# Sheet2_1.net
KiCad netlist of a schematic drawn in Altium Designer
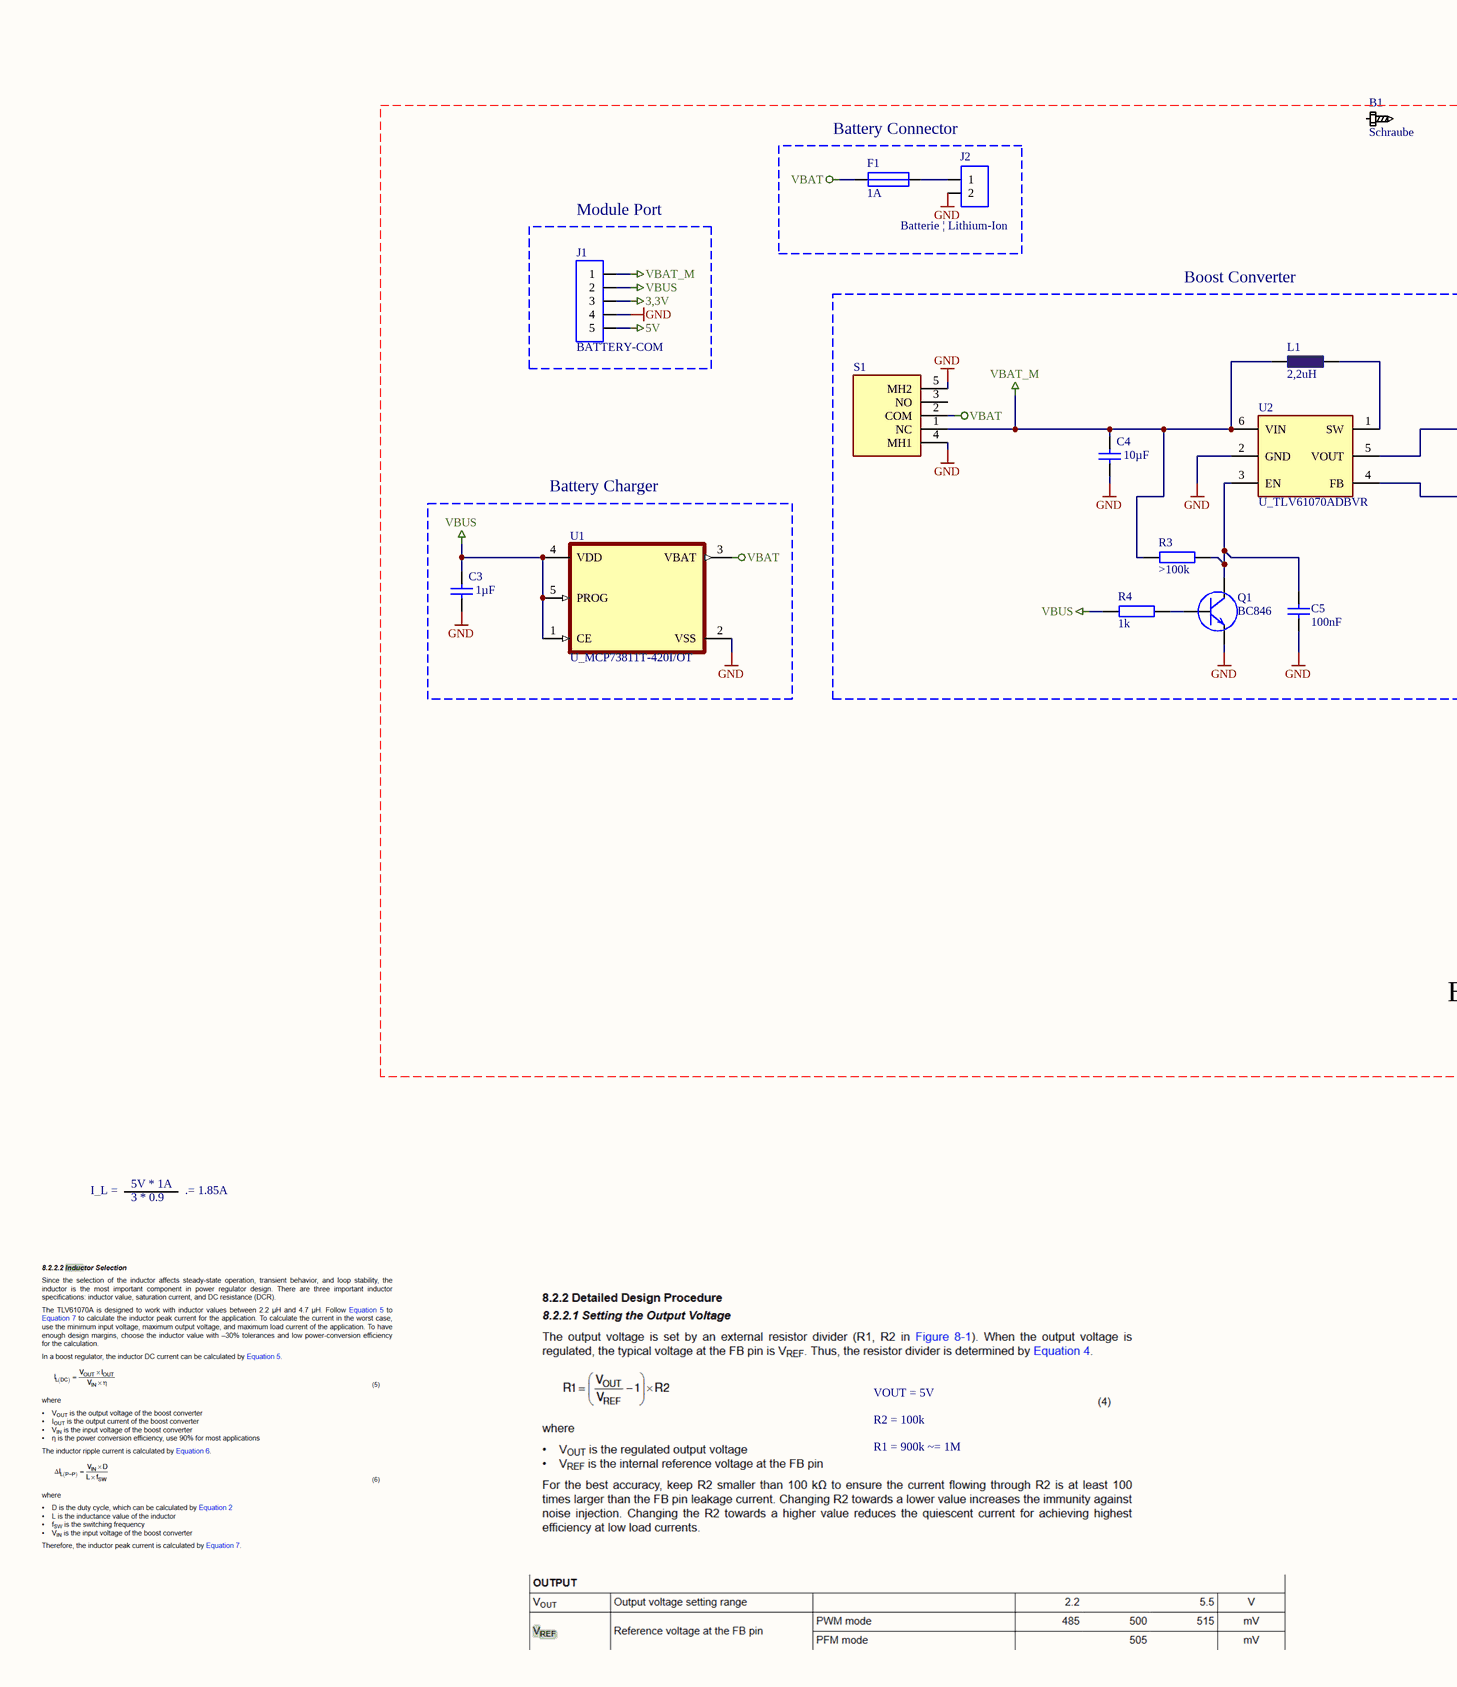
[diagram p0: Sheet2 (1).SchDoc, left]
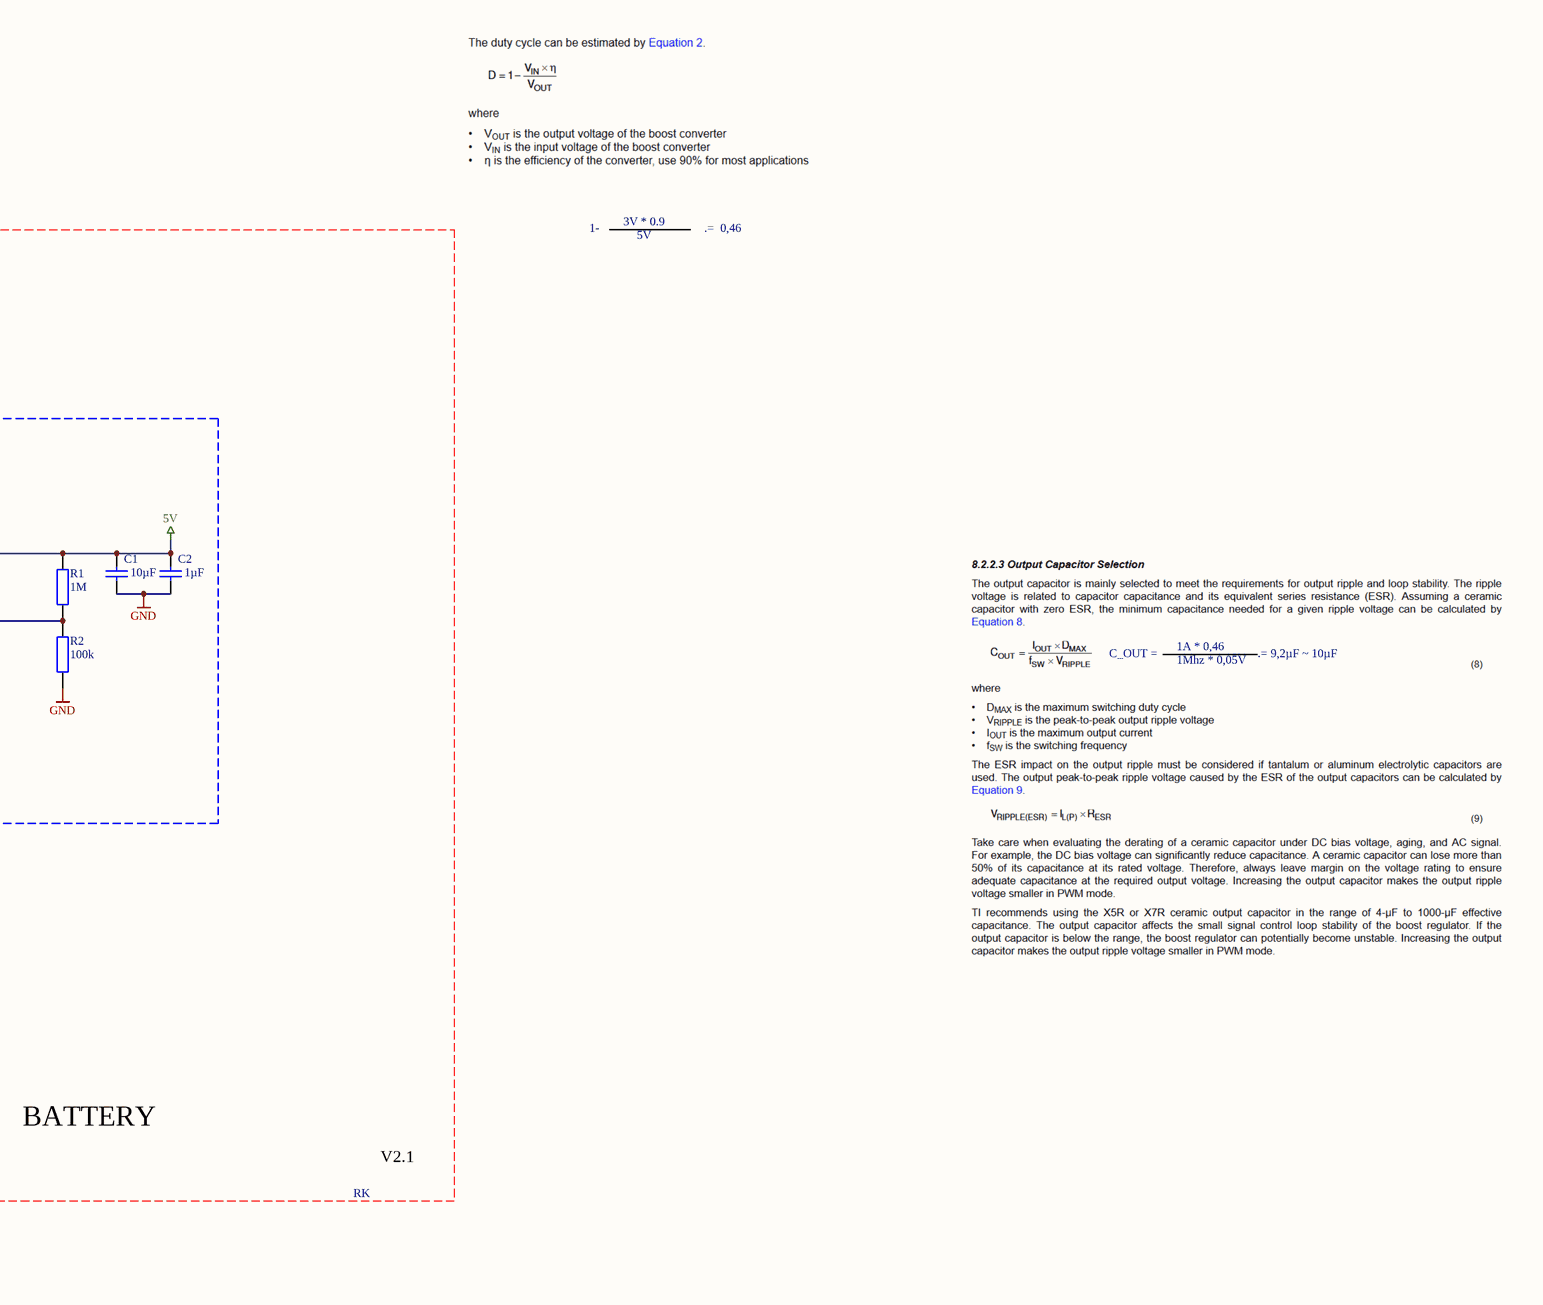
[diagram p1: Sheet2 (1).SchDoc, right]

(export (version "E")
  (design (tool "Eeschema 10.0.6"))
  (components
    (comp (ref "B1")
      (value "Schraube")
      (footprint "B_Schraube-M3 PAD")
      (description "Schraubenloch für M3 Schrauben")
      (libsource (lib "SCHLIB-PCSB_5.1.3") (part "B_Schraube"))
    )
    (comp (ref "C1")
      (value "10µF")
      (footprint "C_SMD_0805")
      (description "Kondensator SMD Universal, Keramik, Folie, usw.")
      (libsource (lib "SCHLIB-PCSB_5.1.3") (part "C_SMD_KO"))
    )
    (comp (ref "C2")
      (value "1µF")
      (footprint "C_SMD_0603")
      (description "Kondensator SMD Universal, Keramik, Folie, usw.")
      (libsource (lib "SCHLIB-PCSB_5.1.3") (part "C_SMD_KO"))
    )
    (comp (ref "C3")
      (value "1µF")
      (footprint "C_SMD_0603")
      (description "Kondensator SMD Universal, Keramik, Folie, usw.")
      (libsource (lib "SCHLIB-PCSB_5.1.3") (part "C_SMD_KO"))
    )
    (comp (ref "C4")
      (value "10µF")
      (footprint "C_SMD_0805")
      (description "Kondensator SMD Universal, Keramik, Folie, usw.")
      (libsource (lib "SCHLIB-PCSB_5.1.3") (part "C_SMD_KO"))
    )
    (comp (ref "C5")
      (value "100nF")
      (footprint "C_SMD_0603")
      (description "Kondensator SMD Universal, Keramik, Folie, usw.")
      (libsource (lib "SCHLIB-PCSB_5.1.3") (part "C_SMD_KO"))
    )
    (comp (ref "F1")
      (value "1A")
      (footprint "F_OMF63_Schurtner")
      (description "Sicherung")
      (libsource (lib "SCHLIB-PCSB_5.1.3") (part "F_THT_Fuse"))
    )
    (comp (ref "J1")
      (value "BATTERY-COM")
      (footprint "SIP-5")
      (description "Stecker")
      (libsource (lib "SCHLIB-PCSB_5.1.3") (part "J_THT_CON5"))
    )
    (comp (ref "J2")
      (value "Batterie ¦ Lithium-Ion")
      (footprint "J_THT_Printklemme 2x")
      (description "Stecker")
      (libsource (lib "SCHLIB-PCSB_5.1.3") (part "J_THT_CON2"))
    )
    (comp (ref "L1")
      (value "2,2uH")
      (footprint "L_SMD_74438357100")
      (description "Spule SMD")
      (libsource (lib "SCHLIB-PCSB_5.1.3") (part "L_SMD_Spule"))
    )
    (comp (ref "Q1")
      (value "BC846")
      (footprint "SOT-23-3_BC846")
      (description "NPN Transistor")
      (libsource (lib "SCHLIB-PCSB_5.1.3") (part "Q_SMD_NPN"))
    )
    (comp (ref "R1")
      (value "1M")
      (footprint "R_SMD_0805")
      (description "Widerstand SMD")
      (libsource (lib "SCHLIB-PCSB_5.1.3") (part "R_SMD_Widerstand"))
    )
    (comp (ref "R2")
      (value "100k")
      (footprint "R_SMD_0805")
      (description "Widerstand SMD")
      (libsource (lib "SCHLIB-PCSB_5.1.3") (part "R_SMD_Widerstand"))
    )
    (comp (ref "R3")
      (value ">100k")
      (footprint "R_SMD_0603")
      (description "Widerstand SMD")
      (libsource (lib "SCHLIB-PCSB_5.1.3") (part "R_SMD_Widerstand"))
    )
    (comp (ref "R4")
      (value "1k")
      (footprint "R_SMD_0603")
      (description "Widerstand SMD")
      (libsource (lib "SCHLIB-PCSB_5.1.3") (part "R_SMD_Widerstand"))
    )
    (comp (ref "S1")
      (value "S_SLW-1298856-5A-RA-N-D")
      (footprint "SLW12988565ARAND")
      (description "Switch")
      (fields (field (name "MANUFACTURER_PART_NUMBER") "SLW-1298856-5A-RA-N-D"))
      (libsource (lib "SCHLIB-PCSB_5.1.3") (part "S_SLW-1298856-5A-RA-N-D"))
    )
    (comp (ref "U1")
      (value "U_MCP73811T-420I/OT")
      (footprint "SOT95P280X145-5N")
      (description "Charger IC Lithium Ion/Polymer SOT-23-5")
      (fields (field (name "MF") "Microchip") (field (name "MP") "MCP73811T-420I/OT"))
      (libsource (lib "SCHLIB-PCSB_5.1.3") (part "U_MCP73811T-420I/OT"))
    )
    (comp (ref "U2")
      (value "U_TLV61070ADBVR")
      (footprint "SOT23-6")
      (description "Integrated Circuit, Boost converter: Input 0.5 - 5.5V \r\nOutput 2.2 - 5.5V")
      (fields
        (field (name "MANUFACTURER_PART_NUMBER") "TLV61070ADBVR")
        (field (name "MOUSER PART NUMBER") "595-TLV61070ADBVR")
      )
      (libsource (lib "SCHLIB-PCSB_5.1.3") (part "U_TLV61070ADBVR"))
    )
  )
  (nets
    (net (code "1") (name "3,3V") (class "Default")
      (node (ref "J1") (pin "3") (pinfunction "3_3") (pintype "passive"))
    )
    (net (code "2") (name "5V") (class "Default")
      (node (ref "C1") (pin "1") (pintype "passive"))
      (node (ref "C2") (pin "1") (pintype "passive"))
      (node (ref "J1") (pin "5") (pinfunction "5_5") (pintype "passive"))
      (node (ref "R1") (pin "2") (pintype "passive"))
      (node (ref "U2") (pin "5") (pinfunction "VOUT_5") (pintype "passive"))
    )
    (net (code "3") (name "GND") (class "Default")
      (node (ref "C1") (pin "2") (pintype "passive"))
      (node (ref "C2") (pin "2") (pintype "passive"))
      (node (ref "C3") (pin "2") (pintype "passive"))
      (node (ref "C4") (pin "2") (pintype "passive"))
      (node (ref "C5") (pin "2") (pintype "passive"))
      (node (ref "J1") (pin "4") (pinfunction "4_4") (pintype "passive"))
      (node (ref "J2") (pin "2") (pinfunction "2_2") (pintype "passive"))
      (node (ref "Q1") (pin "E") (pinfunction "E_E") (pintype "passive"))
      (node (ref "R2") (pin "1") (pintype "passive"))
      (node (ref "S1") (pin "4") (pinfunction "MH1_4") (pintype "passive"))
      (node (ref "S1") (pin "5") (pinfunction "MH2_5") (pintype "passive"))
      (node (ref "U1") (pin "2") (pinfunction "VSS_2") (pintype "power_in"))
      (node (ref "U2") (pin "2") (pinfunction "GND_2") (pintype "passive"))
    )
    (net (code "4") (name "Net-(F1-Pad2)") (class "Default")
      (node (ref "F1") (pin "2") (pinfunction "2_2") (pintype "passive"))
      (node (ref "J2") (pin "1") (pinfunction "1_1") (pintype "passive"))
    )
    (net (code "5") (name "Net-(Q1-PadB)") (class "Default")
      (node (ref "Q1") (pin "B") (pinfunction "B_B") (pintype "passive"))
      (node (ref "R4") (pin "2") (pintype "passive"))
    )
    (net (code "6") (name "Net-(U2-EN)") (class "Default")
      (node (ref "C5") (pin "1") (pintype "passive"))
      (node (ref "Q1") (pin "C") (pinfunction "C_C") (pintype "passive"))
      (node (ref "R3") (pin "2") (pintype "passive"))
      (node (ref "U2") (pin "3") (pinfunction "EN_3") (pintype "passive"))
    )
    (net (code "7") (name "Net-(U2-FB)") (class "Default")
      (node (ref "R1") (pin "1") (pintype "passive"))
      (node (ref "R2") (pin "2") (pintype "passive"))
      (node (ref "U2") (pin "4") (pinfunction "FB_4") (pintype "passive"))
    )
    (net (code "8") (name "Net-(U2-SW)") (class "Default")
      (node (ref "L1") (pin "1") (pintype "passive"))
      (node (ref "U2") (pin "1") (pinfunction "SW_1") (pintype "passive"))
    )
    (net (code "9") (name "VBAT") (class "Default")
      (node (ref "F1") (pin "1") (pintype "passive"))
      (node (ref "S1") (pin "2") (pinfunction "COM_2") (pintype "passive"))
      (node (ref "U1") (pin "3") (pinfunction "VBAT_3") (pintype "output"))
    )
    (net (code "10") (name "VBAT_M") (class "Default")
      (node (ref "C4") (pin "1") (pintype "passive"))
      (node (ref "J1") (pin "1") (pinfunction "1_1") (pintype "passive"))
      (node (ref "L1") (pin "2") (pintype "passive"))
      (node (ref "R3") (pin "1") (pintype "passive"))
      (node (ref "S1") (pin "1") (pinfunction "NC_1") (pintype "passive"))
      (node (ref "U2") (pin "6") (pinfunction "VIN_6") (pintype "passive"))
    )
    (net (code "11") (name "VBUS") (class "Default")
      (node (ref "C3") (pin "1") (pintype "passive"))
      (node (ref "J1") (pin "2") (pinfunction "2_2") (pintype "passive"))
      (node (ref "R4") (pin "1") (pintype "passive"))
      (node (ref "U1") (pin "1") (pinfunction "CE_1") (pintype "input"))
      (node (ref "U1") (pin "4") (pinfunction "VDD_4") (pintype "power_in"))
      (node (ref "U1") (pin "5") (pinfunction "PROG_5") (pintype "input"))
    )
    (net (code "12") (name "unconnected-(B1-PAD-Pad1)") (class "Default")
      (node (ref "B1") (pin "1") (pinfunction "PAD_1") (pintype "passive"))
    )
    (net (code "13") (name "unconnected-(S1-NO-Pad3)") (class "Default")
      (node (ref "S1") (pin "3") (pinfunction "NO_3") (pintype "passive"))
    )
  )
)
